# DTMF.net
KiCad netlist of a schematic drawn in EAGLE
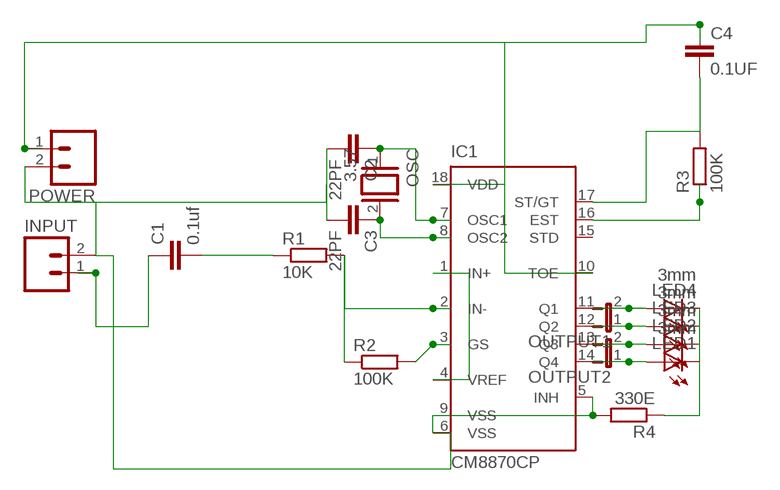
[diagram p0: schematic, sheet 1]

(export (version "E")
  (design (tool "Eeschema 10.0.6"))
  (components
    (comp (ref "C1")
      (value "0.1uf")
      (footprint "eagle-import:C2.5-2")
      (libsource (lib "eagle-import") (part "C2.5/2"))
    )
    (comp (ref "C2")
      (value "22PF")
      (footprint "eagle-import:C2.5-2")
      (libsource (lib "eagle-import") (part "C2.5/2"))
    )
    (comp (ref "C3")
      (value "22PF")
      (footprint "eagle-import:C2.5-2")
      (libsource (lib "eagle-import") (part "C2.5/2"))
    )
    (comp (ref "C4")
      (value "0.1UF")
      (footprint "eagle-import:C2.5-2")
      (libsource (lib "eagle-import") (part "C2.5/2"))
    )
    (comp (ref "IC1")
      (value "CM8870CP")
      (footprint "eagle-import:DIL18")
      (libsource (lib "eagle-import") (part "CM8870CP"))
    )
    (comp (ref "INPUT")
      (value "M02")
      (footprint "eagle-import:02P")
      (libsource (lib "eagle-import") (part "M02"))
    )
    (comp (ref "LED1")
      (value "3mm")
      (footprint "eagle-import:LED3MM")
      (libsource (lib "eagle-import") (part "LED3MM"))
    )
    (comp (ref "LED2")
      (value "3mm")
      (footprint "eagle-import:LED3MM")
      (libsource (lib "eagle-import") (part "LED3MM"))
    )
    (comp (ref "LED3")
      (value "3mm")
      (footprint "eagle-import:LED3MM")
      (libsource (lib "eagle-import") (part "LED3MM"))
    )
    (comp (ref "LED4")
      (value "3mm")
      (footprint "eagle-import:LED3MM")
      (libsource (lib "eagle-import") (part "LED3MM"))
    )
    (comp (ref "OSC")
      (value "3.57")
      (footprint "eagle-import:QS")
      (libsource (lib "eagle-import") (part "XTAL/S"))
    )
    (comp (ref "OUTPUT1")
      (value "JP1E")
      (footprint "eagle-import:JP1")
      (libsource (lib "eagle-import") (part "JP1E"))
    )
    (comp (ref "OUTPUT2")
      (value "JP1E")
      (footprint "eagle-import:JP1")
      (libsource (lib "eagle-import") (part "JP1E"))
    )
    (comp (ref "POWER")
      (value "M02")
      (footprint "eagle-import:02P")
      (libsource (lib "eagle-import") (part "M02"))
    )
    (comp (ref "R1")
      (value "10K")
      (footprint "eagle-import:0204_7")
      (libsource (lib "eagle-import") (part "R-EU_0204/7"))
    )
    (comp (ref "R2")
      (value "100K")
      (footprint "eagle-import:0204_7")
      (libsource (lib "eagle-import") (part "R-EU_0204/7"))
    )
    (comp (ref "R3")
      (value "100K")
      (footprint "eagle-import:0204_7")
      (libsource (lib "eagle-import") (part "R-EU_0204/7"))
    )
    (comp (ref "R4")
      (value "330E")
      (footprint "eagle-import:0204_7")
      (libsource (lib "eagle-import") (part "R-EU_0204/7"))
    )
  )
  (nets
    (net (code "1") (name "Net-(C1-Pad1)") (class "Default")
      (node (ref "C1") (pin "1") (pinfunction "1_1") (pintype "passive"))
      (node (ref "INPUT") (pin "1") (pinfunction "1_1") (pintype "passive"))
    )
    (net (code "2") (name "Net-(C1-Pad2)") (class "Default")
      (node (ref "C1") (pin "2") (pinfunction "2_2") (pintype "passive"))
      (node (ref "R1") (pin "1") (pinfunction "1_1") (pintype "passive"))
    )
    (net (code "3") (name "Net-(IC1-EST)") (class "Default")
      (node (ref "IC1") (pin "16") (pinfunction "EST_16") (pintype "input"))
      (node (ref "R3") (pin "1") (pinfunction "1_1") (pintype "passive"))
    )
    (net (code "4") (name "Net-(IC1-GS)") (class "Default")
      (node (ref "IC1") (pin "3") (pinfunction "GS_3") (pintype "input"))
      (node (ref "R2") (pin "2") (pinfunction "2_2") (pintype "passive"))
    )
    (net (code "5") (name "Net-(IC1-IN+)") (class "Default")
      (node (ref "IC1") (pin "1") (pinfunction "IN+_1") (pintype "input"))
      (node (ref "IC1") (pin "4") (pinfunction "VREF_4") (pintype "output"))
    )
    (net (code "6") (name "Net-(IC1-IN-)") (class "Default")
      (node (ref "IC1") (pin "2") (pinfunction "IN-_2") (pintype "input"))
      (node (ref "R1") (pin "2") (pinfunction "2_2") (pintype "passive"))
      (node (ref "R2") (pin "1") (pinfunction "1_1") (pintype "passive"))
    )
    (net (code "7") (name "Net-(IC1-INH)") (class "Default")
      (node (ref "C2") (pin "2") (pinfunction "2_2") (pintype "passive"))
      (node (ref "C3") (pin "2") (pinfunction "2_2") (pintype "passive"))
      (node (ref "IC1") (pin "5") (pinfunction "INH_5") (pintype "input"))
      (node (ref "IC1") (pin "6") (pinfunction "VSS_6") (pintype "power_in"))
      (node (ref "IC1") (pin "9") (pinfunction "VSS_9") (pintype "power_in"))
      (node (ref "INPUT") (pin "2") (pinfunction "2_2") (pintype "passive"))
      (node (ref "POWER") (pin "2") (pinfunction "2_2") (pintype "passive"))
      (node (ref "R4") (pin "2") (pinfunction "2_2") (pintype "passive"))
    )
    (net (code "8") (name "Net-(IC1-OSC1)") (class "Default")
      (node (ref "C2") (pin "1") (pinfunction "1_1") (pintype "passive"))
      (node (ref "IC1") (pin "7") (pinfunction "OSC1_7") (pintype "input"))
      (node (ref "OSC") (pin "1") (pinfunction "1_1") (pintype "passive"))
    )
    (net (code "9") (name "Net-(IC1-OSC2)") (class "Default")
      (node (ref "C3") (pin "1") (pinfunction "1_1") (pintype "passive"))
      (node (ref "IC1") (pin "8") (pinfunction "OSC2_8") (pintype "bidirectional"))
      (node (ref "OSC") (pin "2") (pinfunction "2_2") (pintype "passive"))
    )
    (net (code "10") (name "Net-(IC1-Q1)") (class "Default")
      (node (ref "IC1") (pin "11") (pinfunction "Q1_11") (pintype "output"))
      (node (ref "LED4") (pin "A") (pinfunction "A_A") (pintype "passive"))
      (node (ref "OUTPUT1") (pin "2") (pinfunction "2_2") (pintype "passive"))
    )
    (net (code "11") (name "Net-(IC1-Q2)") (class "Default")
      (node (ref "IC1") (pin "12") (pinfunction "Q2_12") (pintype "output"))
      (node (ref "LED3") (pin "A") (pinfunction "A_A") (pintype "passive"))
      (node (ref "OUTPUT1") (pin "1") (pinfunction "1_1") (pintype "passive"))
    )
    (net (code "12") (name "Net-(IC1-Q3)") (class "Default")
      (node (ref "IC1") (pin "13") (pinfunction "Q3_13") (pintype "output"))
      (node (ref "LED2") (pin "A") (pinfunction "A_A") (pintype "passive"))
      (node (ref "OUTPUT2") (pin "2") (pinfunction "2_2") (pintype "passive"))
    )
    (net (code "13") (name "Net-(IC1-Q4)") (class "Default")
      (node (ref "IC1") (pin "14") (pinfunction "Q4_14") (pintype "output"))
      (node (ref "LED1") (pin "A") (pinfunction "A_A") (pintype "passive"))
      (node (ref "OUTPUT2") (pin "1") (pinfunction "1_1") (pintype "passive"))
    )
    (net (code "14") (name "Net-(IC1-ST{slash}GT)") (class "Default")
      (node (ref "C4") (pin "2") (pinfunction "2_2") (pintype "passive"))
      (node (ref "IC1") (pin "17") (pinfunction "ST/GT_17") (pintype "bidirectional"))
      (node (ref "R3") (pin "2") (pinfunction "2_2") (pintype "passive"))
    )
    (net (code "15") (name "Net-(IC1-TOE)") (class "Default")
      (node (ref "C4") (pin "1") (pinfunction "1_1") (pintype "passive"))
      (node (ref "IC1") (pin "10") (pinfunction "TOE_10") (pintype "input"))
      (node (ref "IC1") (pin "18") (pinfunction "VDD_18") (pintype "power_in"))
      (node (ref "POWER") (pin "1") (pinfunction "1_1") (pintype "passive"))
    )
    (net (code "16") (name "Net-(LED1-C)") (class "Default")
      (node (ref "LED1") (pin "K") (pinfunction "C_K") (pintype "passive"))
      (node (ref "LED2") (pin "K") (pinfunction "C_K") (pintype "passive"))
      (node (ref "LED3") (pin "K") (pinfunction "C_K") (pintype "passive"))
      (node (ref "LED4") (pin "K") (pinfunction "C_K") (pintype "passive"))
      (node (ref "R4") (pin "1") (pinfunction "1_1") (pintype "passive"))
    )
    (net (code "17") (name "unconnected-(IC1-STD-Pad15)") (class "Default")
      (node (ref "IC1") (pin "15") (pinfunction "STD_15") (pintype "input"))
    )
  )
)
